# MAM_GND_V5.net
KiCad netlist of a schematic drawn in EAGLE
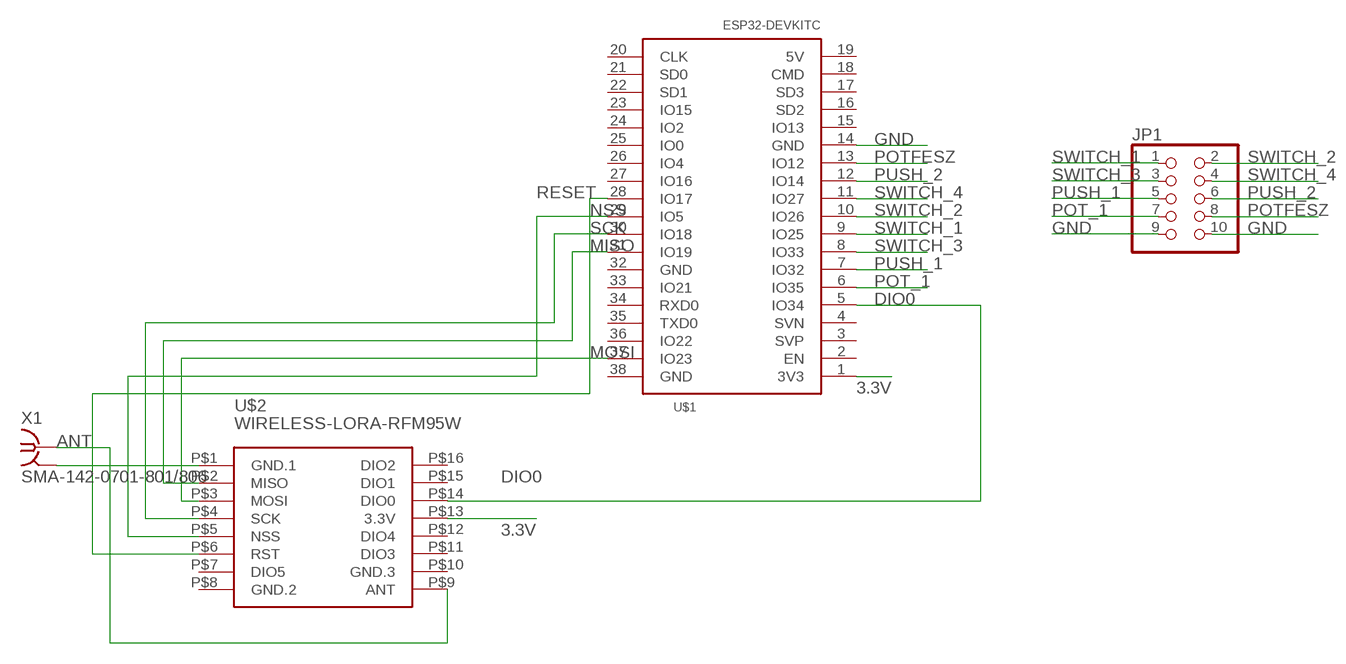
[diagram p0: schematic, sheet 1]

(export (version "E")
  (design (tool "Eeschema 10.0.6"))
  (components
    (comp (ref "JP1")
      (value "PINHD-2X5")
      (footprint "eagle-import:2X05")
      (libsource (lib "eagle-import") (part "PINHD-2X5"))
    )
    (comp (ref "U$1")
      (value "ESP32DEVKITC")
      (footprint "eagle-import:ESP32-DEVKITC")
      (libsource (lib "eagle-import") (part "ESP32DEVKITC"))
    )
    (comp (ref "U$2")
      (value "WIRELESS-LORA-RFM95W")
      (footprint "eagle-import:LORA-BREAKOUT")
      (libsource (lib "eagle-import") (part "WIRELESS-LORA-RFM95W"))
    )
    (comp (ref "X1")
      (value "SMA-142-0701-801/806")
      (footprint "eagle-import:J502-ND-142-0701-801_806")
      (fields (field (name "MF") "JOHNSON COMPONENTS") (field (name "MPN") "142-0701-801"))
      (libsource (lib "eagle-import") (part "SMA-142-0701-801/806"))
    )
  )
  (nets
    (net (code "1") (name "/3.3V") (class "Default")
      (node (ref "U$1") (pin "1") (pinfunction "3V3_1") (pintype "bidirectional"))
      (node (ref "U$2") (pin "P$13") (pinfunction "3.3V_P$13") (pintype "power_in"))
    )
    (net (code "2") (name "/ANT") (class "Default")
      (node (ref "U$2") (pin "P$9") (pinfunction "ANT_P$9") (pintype "passive"))
      (node (ref "X1") (pin "1") (pinfunction "1_1") (pintype "passive"))
    )
    (net (code "3") (name "/DIO0") (class "Default")
      (node (ref "U$1") (pin "5") (pinfunction "IO34_5") (pintype "bidirectional"))
      (node (ref "U$2") (pin "P$14") (pinfunction "DIO0_P$14") (pintype "bidirectional"))
    )
    (net (code "4") (name "/GND") (class "Default")
      (node (ref "JP1") (pin "10") (pinfunction "10_10") (pintype "passive"))
      (node (ref "JP1") (pin "9") (pinfunction "9_9") (pintype "passive"))
      (node (ref "U$1") (pin "14") (pinfunction "GND_14") (pintype "bidirectional"))
      (node (ref "U$2") (pin "P$1") (pinfunction "GND.1_P$1") (pintype "power_in"))
      (node (ref "X1") (pin "G@1") (pinfunction "2_G@1") (pintype "passive"))
      (node (ref "X1") (pin "G@2") (pinfunction "2_G@2") (pintype "passive"))
      (node (ref "X1") (pin "G@3") (pinfunction "2_G@3") (pintype "passive"))
      (node (ref "X1") (pin "G@4") (pinfunction "2_G@4") (pintype "passive"))
    )
    (net (code "5") (name "/GND.2") (class "Default")
      (node (ref "U$2") (pin "P$8") (pinfunction "GND.2_P$8") (pintype "power_in"))
    )
    (net (code "6") (name "/GND.3") (class "Default")
      (node (ref "U$2") (pin "P$10") (pinfunction "GND.3_P$10") (pintype "power_in"))
    )
    (net (code "7") (name "/MISO") (class "Default")
      (node (ref "U$1") (pin "31") (pinfunction "IO19_31") (pintype "bidirectional"))
      (node (ref "U$2") (pin "P$2") (pinfunction "MISO_P$2") (pintype "bidirectional"))
    )
    (net (code "8") (name "/MOSI") (class "Default")
      (node (ref "U$1") (pin "37") (pinfunction "IO23_37") (pintype "bidirectional"))
      (node (ref "U$2") (pin "P$3") (pinfunction "MOSI_P$3") (pintype "bidirectional"))
    )
    (net (code "9") (name "/NSS") (class "Default")
      (node (ref "U$1") (pin "29") (pinfunction "IO5_29") (pintype "bidirectional"))
      (node (ref "U$2") (pin "P$5") (pinfunction "NSS_P$5") (pintype "bidirectional"))
    )
    (net (code "10") (name "/POTFESZ") (class "Default")
      (node (ref "JP1") (pin "8") (pinfunction "8_8") (pintype "passive"))
      (node (ref "U$1") (pin "13") (pinfunction "IO12_13") (pintype "bidirectional"))
    )
    (net (code "11") (name "/POT_1") (class "Default")
      (node (ref "JP1") (pin "7") (pinfunction "7_7") (pintype "passive"))
      (node (ref "U$1") (pin "6") (pinfunction "IO35_6") (pintype "bidirectional"))
    )
    (net (code "12") (name "/PUSH_1") (class "Default")
      (node (ref "JP1") (pin "5") (pinfunction "5_5") (pintype "passive"))
      (node (ref "U$1") (pin "7") (pinfunction "IO32_7") (pintype "bidirectional"))
    )
    (net (code "13") (name "/PUSH_2") (class "Default")
      (node (ref "JP1") (pin "6") (pinfunction "6_6") (pintype "passive"))
      (node (ref "U$1") (pin "12") (pinfunction "IO14_12") (pintype "bidirectional"))
    )
    (net (code "14") (name "/RESET") (class "Default")
      (node (ref "U$1") (pin "28") (pinfunction "IO17_28") (pintype "bidirectional"))
      (node (ref "U$2") (pin "P$6") (pinfunction "RST_P$6") (pintype "bidirectional"))
    )
    (net (code "15") (name "/SCK") (class "Default")
      (node (ref "U$1") (pin "30") (pinfunction "IO18_30") (pintype "bidirectional"))
      (node (ref "U$2") (pin "P$4") (pinfunction "SCK_P$4") (pintype "bidirectional"))
    )
    (net (code "16") (name "/SWITCH_1") (class "Default")
      (node (ref "JP1") (pin "1") (pinfunction "1_1") (pintype "passive"))
      (node (ref "U$1") (pin "9") (pinfunction "IO25_9") (pintype "bidirectional"))
    )
    (net (code "17") (name "/SWITCH_2") (class "Default")
      (node (ref "JP1") (pin "2") (pinfunction "2_2") (pintype "passive"))
      (node (ref "U$1") (pin "10") (pinfunction "IO26_10") (pintype "bidirectional"))
    )
    (net (code "18") (name "/SWITCH_3") (class "Default")
      (node (ref "JP1") (pin "3") (pinfunction "3_3") (pintype "passive"))
      (node (ref "U$1") (pin "8") (pinfunction "IO33_8") (pintype "bidirectional"))
    )
    (net (code "19") (name "/SWITCH_4") (class "Default")
      (node (ref "JP1") (pin "4") (pinfunction "4_4") (pintype "passive"))
      (node (ref "U$1") (pin "11") (pinfunction "IO27_11") (pintype "bidirectional"))
    )
    (net (code "20") (name "unconnected-(U$1-5V-Pad19)") (class "Default")
      (node (ref "U$1") (pin "19") (pinfunction "5V_19") (pintype "bidirectional"))
    )
    (net (code "21") (name "unconnected-(U$1-CLK-Pad20)") (class "Default")
      (node (ref "U$1") (pin "20") (pinfunction "CLK_20") (pintype "bidirectional"))
    )
    (net (code "22") (name "unconnected-(U$1-CMD-Pad18)") (class "Default")
      (node (ref "U$1") (pin "18") (pinfunction "CMD_18") (pintype "bidirectional"))
    )
    (net (code "23") (name "unconnected-(U$1-EN-Pad2)") (class "Default")
      (node (ref "U$1") (pin "2") (pinfunction "EN_2") (pintype "bidirectional"))
    )
    (net (code "24") (name "unconnected-(U$1-GND-Pad32)") (class "Default")
      (node (ref "U$1") (pin "32") (pinfunction "GND_32") (pintype "bidirectional"))
    )
    (net (code "25") (name "unconnected-(U$1-GND-Pad38)") (class "Default")
      (node (ref "U$1") (pin "38") (pinfunction "GND_38") (pintype "bidirectional"))
    )
    (net (code "26") (name "unconnected-(U$1-IO0-Pad25)") (class "Default")
      (node (ref "U$1") (pin "25") (pinfunction "IO0_25") (pintype "bidirectional"))
    )
    (net (code "27") (name "unconnected-(U$1-IO2-Pad24)") (class "Default")
      (node (ref "U$1") (pin "24") (pinfunction "IO2_24") (pintype "bidirectional"))
    )
    (net (code "28") (name "unconnected-(U$1-IO4-Pad26)") (class "Default")
      (node (ref "U$1") (pin "26") (pinfunction "IO4_26") (pintype "bidirectional"))
    )
    (net (code "29") (name "unconnected-(U$1-IO13-Pad15)") (class "Default")
      (node (ref "U$1") (pin "15") (pinfunction "IO13_15") (pintype "bidirectional"))
    )
    (net (code "30") (name "unconnected-(U$1-IO15-Pad23)") (class "Default")
      (node (ref "U$1") (pin "23") (pinfunction "IO15_23") (pintype "bidirectional"))
    )
    (net (code "31") (name "unconnected-(U$1-IO16-Pad27)") (class "Default")
      (node (ref "U$1") (pin "27") (pinfunction "IO16_27") (pintype "bidirectional"))
    )
    (net (code "32") (name "unconnected-(U$1-IO21-Pad33)") (class "Default")
      (node (ref "U$1") (pin "33") (pinfunction "IO21_33") (pintype "bidirectional"))
    )
    (net (code "33") (name "unconnected-(U$1-IO22-Pad36)") (class "Default")
      (node (ref "U$1") (pin "36") (pinfunction "IO22_36") (pintype "bidirectional"))
    )
    (net (code "34") (name "unconnected-(U$1-RXD0-Pad34)") (class "Default")
      (node (ref "U$1") (pin "34") (pinfunction "RXD0_34") (pintype "bidirectional"))
    )
    (net (code "35") (name "unconnected-(U$1-SD0-Pad21)") (class "Default")
      (node (ref "U$1") (pin "21") (pinfunction "SD0_21") (pintype "bidirectional"))
    )
    (net (code "36") (name "unconnected-(U$1-SD1-Pad22)") (class "Default")
      (node (ref "U$1") (pin "22") (pinfunction "SD1_22") (pintype "bidirectional"))
    )
    (net (code "37") (name "unconnected-(U$1-SD2-Pad16)") (class "Default")
      (node (ref "U$1") (pin "16") (pinfunction "SD2_16") (pintype "bidirectional"))
    )
    (net (code "38") (name "unconnected-(U$1-SD3-Pad17)") (class "Default")
      (node (ref "U$1") (pin "17") (pinfunction "SD3_17") (pintype "bidirectional"))
    )
    (net (code "39") (name "unconnected-(U$1-SVN-Pad4)") (class "Default")
      (node (ref "U$1") (pin "4") (pinfunction "SVN_4") (pintype "bidirectional"))
    )
    (net (code "40") (name "unconnected-(U$1-SVP-Pad3)") (class "Default")
      (node (ref "U$1") (pin "3") (pinfunction "SVP_3") (pintype "bidirectional"))
    )
    (net (code "41") (name "unconnected-(U$1-TXD0-Pad35)") (class "Default")
      (node (ref "U$1") (pin "35") (pinfunction "TXD0_35") (pintype "bidirectional"))
    )
    (net (code "42") (name "unconnected-(U$2-DIO1-PadP$15)") (class "Default")
      (node (ref "U$2") (pin "P$15") (pinfunction "DIO1_P$15") (pintype "bidirectional"))
    )
    (net (code "43") (name "unconnected-(U$2-DIO2-PadP$16)") (class "Default")
      (node (ref "U$2") (pin "P$16") (pinfunction "DIO2_P$16") (pintype "bidirectional"))
    )
    (net (code "44") (name "unconnected-(U$2-DIO3-PadP$11)") (class "Default")
      (node (ref "U$2") (pin "P$11") (pinfunction "DIO3_P$11") (pintype "bidirectional"))
    )
    (net (code "45") (name "unconnected-(U$2-DIO4-PadP$12)") (class "Default")
      (node (ref "U$2") (pin "P$12") (pinfunction "DIO4_P$12") (pintype "bidirectional"))
    )
    (net (code "46") (name "unconnected-(U$2-DIO5-PadP$7)") (class "Default")
      (node (ref "U$2") (pin "P$7") (pinfunction "DIO5_P$7") (pintype "bidirectional"))
    )
  )
)
